# CH573.net
KiCad netlist of a schematic drawn in Altium Designer
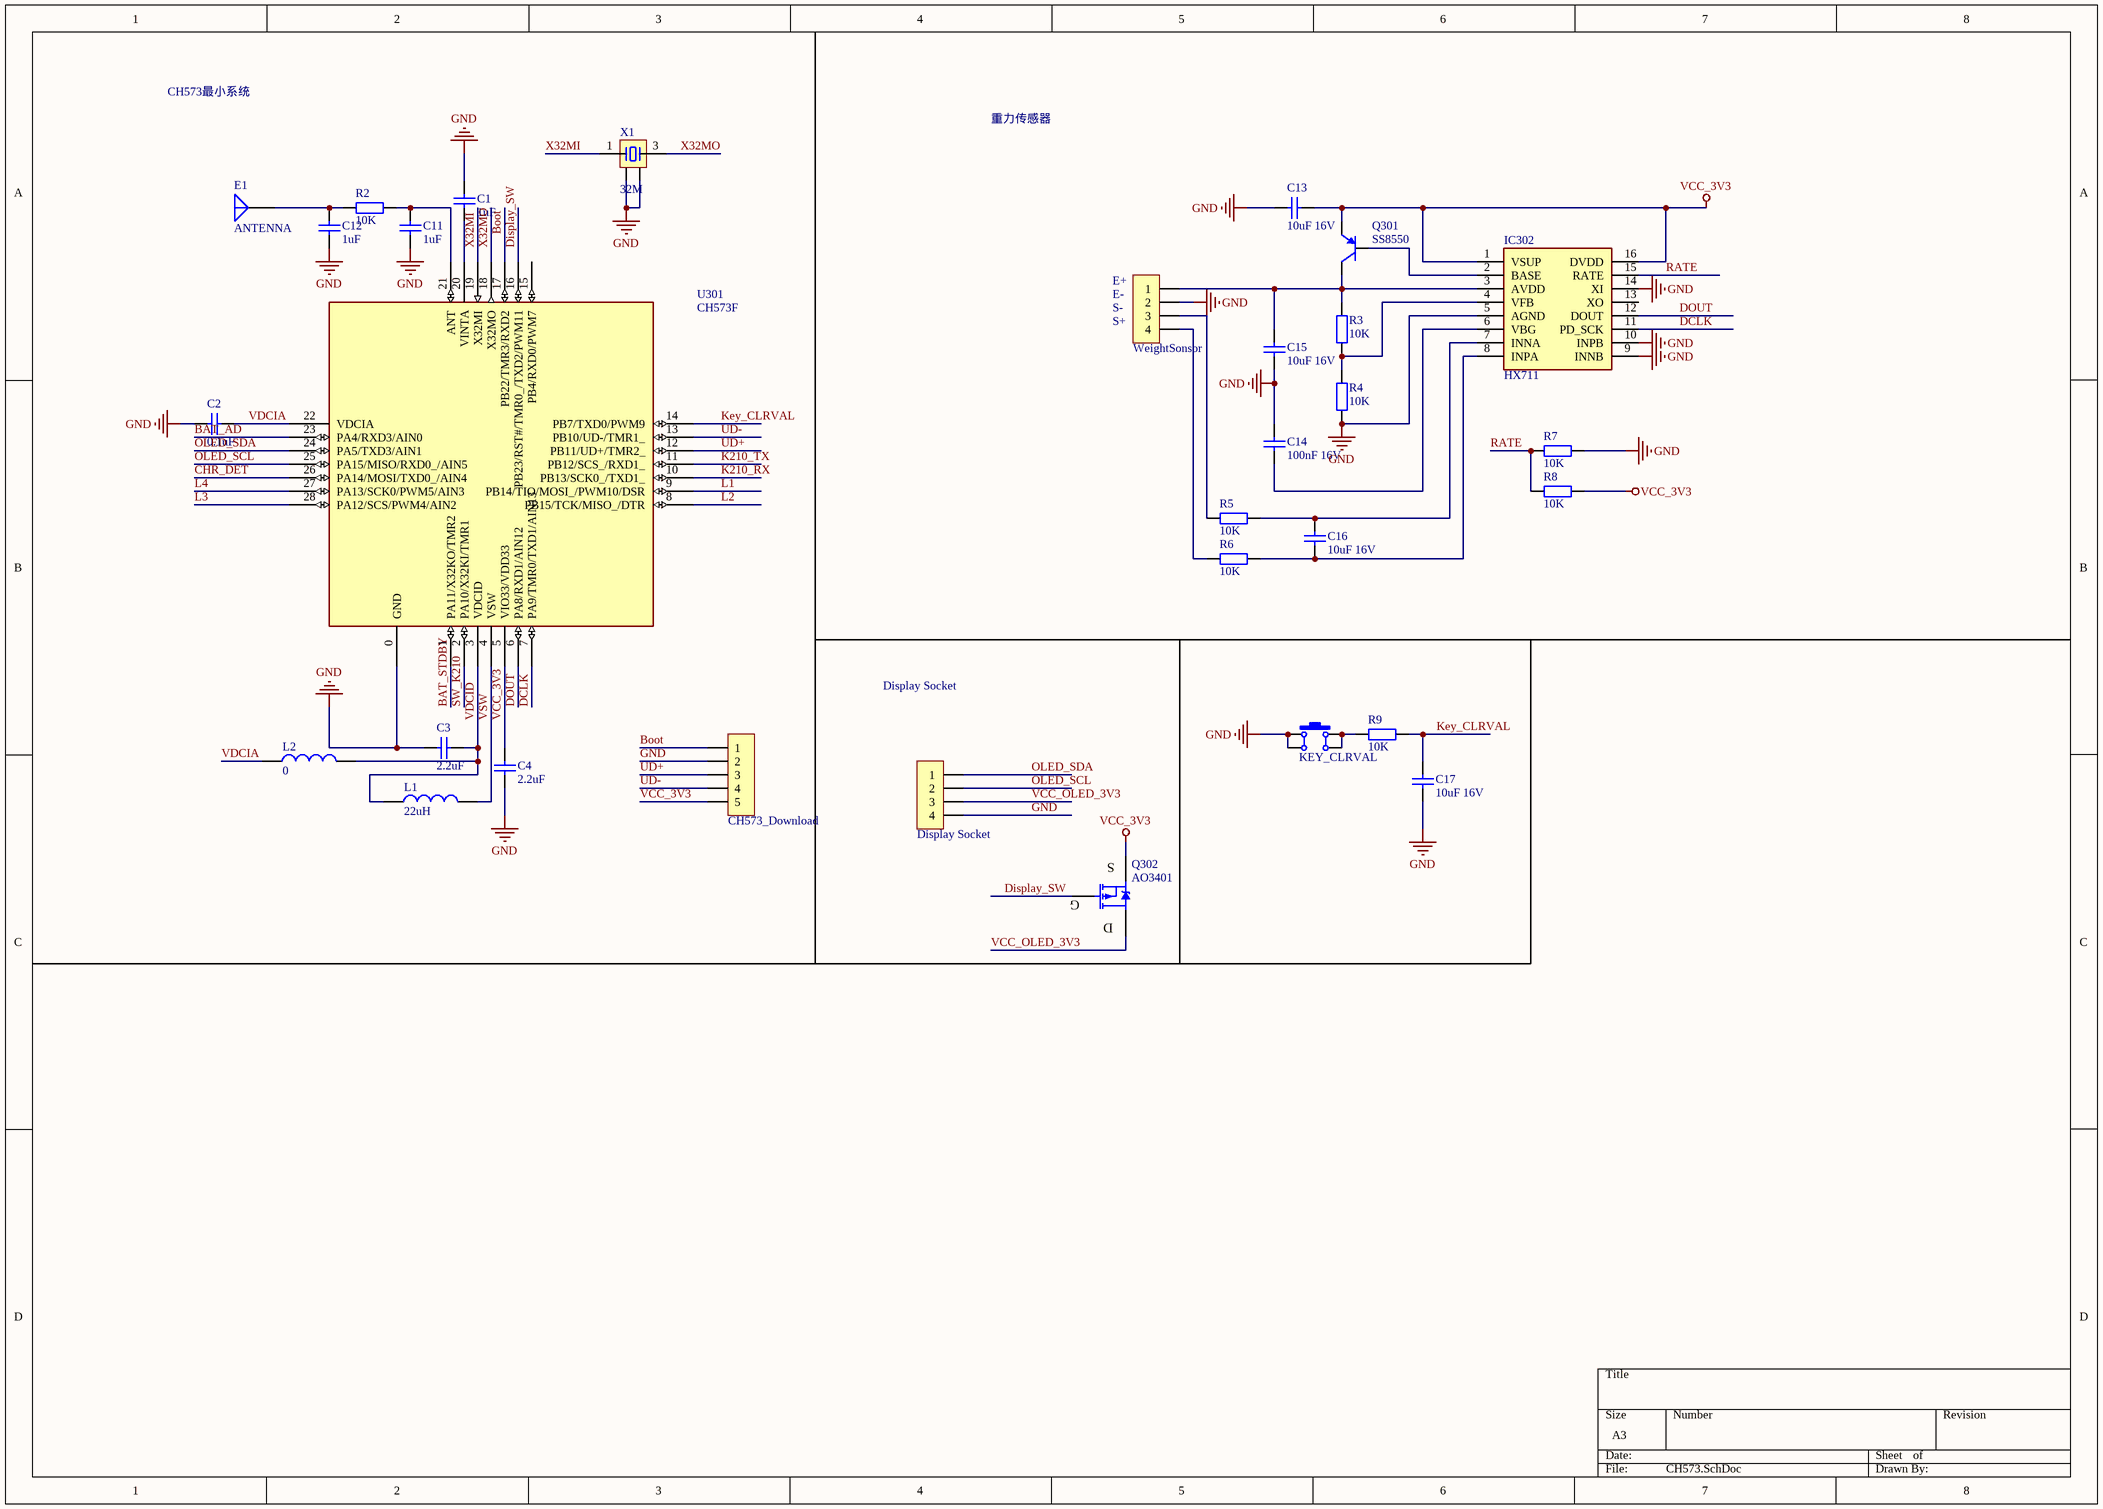
[diagram p0: CH573.SchDoc]

(export (version "E")
  (design (tool "Eeschema 10.0.6"))
  (components
    (comp (ref "C1")
      (value "1uF")
      (footprint "C0603_L")
      (description "贴片电容/MLCC电容")
      (libsource (lib "0.1 - 电阻-电容-电感-晶振-晶体-磁珠-电位器-法拉电容-馈通电容") (part "C"))
    )
    (comp (ref "C2")
      (value "0.1uF")
      (footprint "C0603_L")
      (description "贴片电容/MLCC电容")
      (libsource (lib "0.1 - 电阻-电容-电感-晶振-晶体-磁珠-电位器-法拉电容-馈通电容") (part "C"))
    )
    (comp (ref "C3")
      (value "2.2uF")
      (footprint "C0603_L")
      (description "贴片电容/MLCC电容")
      (libsource (lib "0.1 - 电阻-电容-电感-晶振-晶体-磁珠-电位器-法拉电容-馈通电容") (part "C"))
    )
    (comp (ref "C4")
      (value "2.2uF")
      (footprint "C0603_L")
      (description "贴片电容/MLCC电容")
      (libsource (lib "0.1 - 电阻-电容-电感-晶振-晶体-磁珠-电位器-法拉电容-馈通电容") (part "C"))
    )
    (comp (ref "C11")
      (value "1uF")
      (footprint "C0201_L")
      (description "贴片电容/MLCC电容")
      (libsource (lib "0.1 - 电阻-电容-电感-晶振-晶体-磁珠-电位器-法拉电容-馈通电容") (part "C"))
    )
    (comp (ref "C12")
      (value "1uF")
      (footprint "C0201_L")
      (description "贴片电容/MLCC电容")
      (libsource (lib "0.1 - 电阻-电容-电感-晶振-晶体-磁珠-电位器-法拉电容-馈通电容") (part "C"))
    )
    (comp (ref "C13")
      (value "10uF 16V")
      (footprint "C0805_L")
      (description "贴片电容/MLCC电容")
      (libsource (lib "0.1 - 电阻-电容-电感-晶振-晶体-磁珠-电位器-法拉电容-馈通电容") (part "C"))
    )
    (comp (ref "C14")
      (value "100nF 16V")
      (footprint "C0603_L")
      (description "贴片电容/MLCC电容")
      (libsource (lib "0.1 - 电阻-电容-电感-晶振-晶体-磁珠-电位器-法拉电容-馈通电容") (part "C"))
    )
    (comp (ref "C15")
      (value "10uF 16V")
      (footprint "C0603_L")
      (description "贴片电容/MLCC电容")
      (libsource (lib "0.1 - 电阻-电容-电感-晶振-晶体-磁珠-电位器-法拉电容-馈通电容") (part "C"))
    )
    (comp (ref "C16")
      (value "10uF 16V")
      (footprint "C0603_L")
      (description "贴片电容/MLCC电容")
      (libsource (lib "0.1 - 电阻-电容-电感-晶振-晶体-磁珠-电位器-法拉电容-馈通电容") (part "C"))
    )
    (comp (ref "C17")
      (value "10uF 16V")
      (footprint "C0603_L")
      (description "贴片电容/MLCC电容")
      (libsource (lib "0.1 - 电阻-电容-电感-晶振-晶体-磁珠-电位器-法拉电容-馈通电容") (part "C"))
    )
    (comp (ref "CH573_Download")
      (value "HDR-1X5")
      (footprint "MX1.25-L-5P")
      (description "5P连接器")
      (libsource (lib "5.1 - 1.25mm连接器(FPC1.25_GH1.25_MX1.25)") (part "Header 5"))
    )
    (comp (ref "Display Socket")
      (value "HDR-1X4")
      (footprint "HDR2.54-M-LI-4P")
      (description "4P接插件")
      (libsource (lib "5.5 - 2.54mm连接器(KF2EDGK_XH2.54_2.54排针排母)") (part "Header 4"))
    )
    (comp (ref "E1")
      (value "ANTENNA")
      (footprint "ANT-F-1-2.4G-1.6")
      (description "Generic Antenna")
      (libsource (lib "CH573F-R0") (part "ANTENNA"))
    )
    (comp (ref "IC302")
      (value "HX711")
      (footprint "SamacSys:SOIC127P600X160-16N")
      (description "Integrated Circuit")
      (libsource (lib "SamacSys") (part "HX711"))
    )
    (comp (ref "KEY_CLRVAL")
      (value "4x4x1.5")
      (footprint "SW SMD-4*4*1.5")
      (description "贴片4x4轻触开关")
      (libsource (lib "0.5 - 按键_开关_蜂鸣器_保险丝_电池_测试点_Mark点_铜柱") (part "SW SMD-4x4"))
    )
    (comp (ref "L1")
      (value "22uH")
      (footprint "L0603")
      (description "贴片小功率电感")
      (libsource (lib "0.1 - 电阻-电容-电感-晶振-晶体-磁珠-电位器-法拉电容-馈通电容") (part "L"))
    )
    (comp (ref "L2")
      (value "0")
      (footprint "L0603")
      (description "贴片小功率电感")
      (libsource (lib "0.1 - 电阻-电容-电感-晶振-晶体-磁珠-电位器-法拉电容-馈通电容") (part "L"))
    )
    (comp (ref "Q301")
      (value "SS8550")
      (footprint "SOT23-3N")
      (description "高频放大-PNP型")
      (libsource (lib "0.4 - 三极管-场效应管-可控硅") (part "8550-SMD"))
    )
    (comp (ref "Q302")
      (value "AO3401")
      (footprint "SOT23-3N")
      (description "P沟道 30V/4.2A")
      (libsource (lib "0.4 - 三极管-场效应管-可控硅") (part "AO3401"))
    )
    (comp (ref "R2")
      (value "10K")
      (footprint "R0201_L")
      (description "贴片电阻")
      (libsource (lib "0.1 - 电阻-电容-电感-晶振-晶体-磁珠-电位器-法拉电容-馈通电容") (part "R"))
    )
    (comp (ref "R3")
      (value "10K")
      (footprint "R0603_L")
      (description "贴片电阻")
      (libsource (lib "0.1 - 电阻-电容-电感-晶振-晶体-磁珠-电位器-法拉电容-馈通电容") (part "R"))
    )
    (comp (ref "R4")
      (value "10K")
      (footprint "R0603_L")
      (description "贴片电阻")
      (libsource (lib "0.1 - 电阻-电容-电感-晶振-晶体-磁珠-电位器-法拉电容-馈通电容") (part "R"))
    )
    (comp (ref "R5")
      (value "10K")
      (footprint "R0603_L")
      (description "贴片电阻")
      (libsource (lib "0.1 - 电阻-电容-电感-晶振-晶体-磁珠-电位器-法拉电容-馈通电容") (part "R"))
    )
    (comp (ref "R6")
      (value "10K")
      (footprint "R0603_L")
      (description "贴片电阻")
      (libsource (lib "0.1 - 电阻-电容-电感-晶振-晶体-磁珠-电位器-法拉电容-馈通电容") (part "R"))
    )
    (comp (ref "R7")
      (value "10K")
      (footprint "R0603_L")
      (description "贴片电阻")
      (libsource (lib "0.1 - 电阻-电容-电感-晶振-晶体-磁珠-电位器-法拉电容-馈通电容") (part "R"))
    )
    (comp (ref "R8")
      (value "10K")
      (footprint "R0603_L")
      (description "贴片电阻")
      (libsource (lib "0.1 - 电阻-电容-电感-晶振-晶体-磁珠-电位器-法拉电容-馈通电容") (part "R"))
    )
    (comp (ref "R9")
      (value "10K")
      (footprint "R0603_L")
      (description "贴片电阻")
      (libsource (lib "0.1 - 电阻-电容-电感-晶振-晶体-磁珠-电位器-法拉电容-馈通电容") (part "R"))
    )
    (comp (ref "U301")
      (value "CH573F")
      (footprint "QFN28_4X4")
      (description "RISC-V MCU with BLE/USB/ADC/SPI/4*UART")
      (libsource (lib "CH573F-R0") (part "CH573F"))
    )
    (comp (ref "WeightSonsor")
      (value "HDR-1X4")
      (footprint "XH2.54-LI-4P")
      (description "4P接插件")
      (libsource (lib "5.5 - 2.54mm连接器(KF2EDGK_XH2.54_2.54排针排母)") (part "Header 4"))
    )
    (comp (ref "X1")
      (value "32M")
      (footprint "XTAL-3225-4P")
      (description "4脚无源晶振(谐振器）")
      (libsource (lib "0.1 - 电阻-电容-电感-晶振-晶体-磁珠-电位器-法拉电容-馈通电容") (part "XTAL-4P"))
    )
  )
  (nets
    (net (code "1") (name "/BAT_AD") (class "Default")
      (node (ref "U301") (pin "23") (pinfunction "PA4/RXD3/AIN0_23") (pintype "bidirectional"))
    )
    (net (code "2") (name "/BAT_STDBY") (class "Default")
      (node (ref "U301") (pin "1") (pinfunction "PA11/X32KO/TMR2_1") (pintype "bidirectional"))
    )
    (net (code "3") (name "/Boot") (class "Default")
      (node (ref "CH573_Download") (pin "1") (pinfunction "1_1") (pintype "passive"))
      (node (ref "U301") (pin "17") (pinfunction "PB22/TMR3/RXD2_17") (pintype "bidirectional"))
    )
    (net (code "4") (name "/CHR_DET") (class "Default")
      (node (ref "U301") (pin "26") (pinfunction "PA14/MOSI/TXD0_/AIN4_26") (pintype "bidirectional"))
    )
    (net (code "5") (name "/DCLK") (class "Default")
      (node (ref "IC302") (pin "11") (pinfunction "PD_SCK_11") (pintype "passive"))
      (node (ref "U301") (pin "7") (pinfunction "PA9/TMR0/TXD1/AIN13_7") (pintype "bidirectional"))
    )
    (net (code "6") (name "/DOUT") (class "Default")
      (node (ref "IC302") (pin "12") (pinfunction "DOUT_12") (pintype "passive"))
      (node (ref "U301") (pin "6") (pinfunction "PA8/RXD1/AIN12_6") (pintype "bidirectional"))
    )
    (net (code "7") (name "/Display_SW") (class "Default")
      (node (ref "Q302") (pin "1") (pinfunction "G_1") (pintype "passive"))
      (node (ref "U301") (pin "16") (pinfunction "PB23/RST#/TMR0_/TXD2/PWM11_16") (pintype "bidirectional"))
    )
    (net (code "8") (name "/K210_RX") (class "Default")
      (node (ref "U301") (pin "10") (pinfunction "PB13/SCK0_/TXD1__10") (pintype "bidirectional"))
    )
    (net (code "9") (name "/K210_TX") (class "Default")
      (node (ref "U301") (pin "11") (pinfunction "PB12/SCS_/RXD1__11") (pintype "bidirectional"))
    )
    (net (code "10") (name "/Key_CLRVAL") (class "Default")
      (node (ref "C17") (pin "2") (pinfunction "2_2") (pintype "passive"))
      (node (ref "R9") (pin "1") (pinfunction "1_1") (pintype "passive"))
      (node (ref "U301") (pin "14") (pinfunction "PB7/TXD0/PWM9_14") (pintype "bidirectional"))
    )
    (net (code "11") (name "/L1") (class "Default")
      (node (ref "U301") (pin "9") (pinfunction "PB14/TIO/MOSI_/PWM10/DSR_9") (pintype "bidirectional"))
    )
    (net (code "12") (name "/L2") (class "Default")
      (node (ref "U301") (pin "8") (pinfunction "PB15/TCK/MISO_/DTR_8") (pintype "bidirectional"))
    )
    (net (code "13") (name "/L3") (class "Default")
      (node (ref "U301") (pin "28") (pinfunction "PA12/SCS/PWM4/AIN2_28") (pintype "bidirectional"))
    )
    (net (code "14") (name "/L4") (class "Default")
      (node (ref "U301") (pin "27") (pinfunction "PA13/SCK0/PWM5/AIN3_27") (pintype "bidirectional"))
    )
    (net (code "15") (name "/OLED_SCL") (class "Default")
      (node (ref "Display Socket") (pin "2") (pinfunction "2_2") (pintype "passive"))
      (node (ref "U301") (pin "25") (pinfunction "PA15/MISO/RXD0_/AIN5_25") (pintype "bidirectional"))
    )
    (net (code "16") (name "/OLED_SDA") (class "Default")
      (node (ref "Display Socket") (pin "1") (pinfunction "1_1") (pintype "passive"))
      (node (ref "U301") (pin "24") (pinfunction "PA5/TXD3/AIN1_24") (pintype "bidirectional"))
    )
    (net (code "17") (name "/RATE") (class "Default")
      (node (ref "IC302") (pin "15") (pinfunction "RATE_15") (pintype "passive"))
      (node (ref "R7") (pin "2") (pinfunction "2_2") (pintype "passive"))
      (node (ref "R8") (pin "2") (pinfunction "2_2") (pintype "passive"))
    )
    (net (code "18") (name "/SW_K210") (class "Default")
      (node (ref "U301") (pin "2") (pinfunction "PA10/X32KI/TMR1_2") (pintype "bidirectional"))
    )
    (net (code "19") (name "/UD+") (class "Default")
      (node (ref "CH573_Download") (pin "3") (pinfunction "3_3") (pintype "passive"))
      (node (ref "U301") (pin "12") (pinfunction "PB11/UD+/TMR2__12") (pintype "bidirectional"))
    )
    (net (code "20") (name "/UD-") (class "Default")
      (node (ref "CH573_Download") (pin "4") (pinfunction "4_4") (pintype "passive"))
      (node (ref "U301") (pin "13") (pinfunction "PB10/UD-/TMR1__13") (pintype "bidirectional"))
    )
    (net (code "21") (name "/VCC_OLED_3V3") (class "Default")
      (node (ref "Display Socket") (pin "3") (pinfunction "3_3") (pintype "passive"))
      (node (ref "Q302") (pin "3") (pinfunction "D_3") (pintype "passive"))
    )
    (net (code "22") (name "/VDCIA") (class "Default")
      (node (ref "C2") (pin "1") (pinfunction "1_1") (pintype "passive"))
      (node (ref "L2") (pin "1") (pinfunction "1_1") (pintype "passive"))
      (node (ref "U301") (pin "22") (pinfunction "VDCIA_22") (pintype "power_in"))
    )
    (net (code "23") (name "/VDCID") (class "Default")
      (node (ref "C3") (pin "1") (pinfunction "1_1") (pintype "passive"))
      (node (ref "L1") (pin "1") (pinfunction "1_1") (pintype "passive"))
      (node (ref "L2") (pin "2") (pinfunction "2_2") (pintype "passive"))
      (node (ref "U301") (pin "3") (pinfunction "VDCID_3") (pintype "power_in"))
    )
    (net (code "24") (name "/VSW") (class "Default")
      (node (ref "L1") (pin "2") (pinfunction "2_2") (pintype "passive"))
      (node (ref "U301") (pin "4") (pinfunction "VSW_4") (pintype "power_in"))
    )
    (net (code "25") (name "/X32MI") (class "Default")
      (node (ref "U301") (pin "19") (pinfunction "X32MI_19") (pintype "input"))
      (node (ref "X1") (pin "1") (pinfunction "1_1") (pintype "passive"))
    )
    (net (code "26") (name "/X32MO") (class "Default")
      (node (ref "U301") (pin "18") (pinfunction "X32MO_18") (pintype "output"))
      (node (ref "X1") (pin "3") (pinfunction "3_3") (pintype "passive"))
    )
    (net (code "27") (name "GND") (class "Default")
      (node (ref "C1") (pin "2") (pinfunction "2_2") (pintype "passive"))
      (node (ref "C11") (pin "2") (pinfunction "2_2") (pintype "passive"))
      (node (ref "C12") (pin "2") (pinfunction "2_2") (pintype "passive"))
      (node (ref "C13") (pin "1") (pinfunction "1_1") (pintype "passive"))
      (node (ref "C14") (pin "2") (pinfunction "2_2") (pintype "passive"))
      (node (ref "C15") (pin "1") (pinfunction "1_1") (pintype "passive"))
      (node (ref "C17") (pin "1") (pinfunction "1_1") (pintype "passive"))
      (node (ref "C2") (pin "2") (pinfunction "2_2") (pintype "passive"))
      (node (ref "C3") (pin "2") (pinfunction "2_2") (pintype "passive"))
      (node (ref "C4") (pin "2") (pinfunction "2_2") (pintype "passive"))
      (node (ref "CH573_Download") (pin "2") (pinfunction "2_2") (pintype "passive"))
      (node (ref "Display Socket") (pin "4") (pinfunction "4_4") (pintype "passive"))
      (node (ref "IC302") (pin "10") (pinfunction "INPB_10") (pintype "passive"))
      (node (ref "IC302") (pin "14") (pinfunction "XI_14") (pintype "passive"))
      (node (ref "IC302") (pin "5") (pinfunction "AGND_5") (pintype "passive"))
      (node (ref "IC302") (pin "9") (pinfunction "INNB_9") (pintype "passive"))
      (node (ref "KEY_CLRVAL") (pin "1") (pinfunction "1_1") (pintype "passive"))
      (node (ref "KEY_CLRVAL") (pin "4") (pinfunction "4_4") (pintype "passive"))
      (node (ref "R4") (pin "1") (pinfunction "1_1") (pintype "passive"))
      (node (ref "R7") (pin "1") (pinfunction "1_1") (pintype "passive"))
      (node (ref "U301") (pin "0") (pinfunction "GND_0") (pintype "power_in"))
      (node (ref "WeightSonsor") (pin "2") (pinfunction "2_2") (pintype "passive"))
      (node (ref "X1") (pin "2") (pinfunction "2_2") (pintype "passive"))
      (node (ref "X1") (pin "4") (pinfunction "4_4") (pintype "passive"))
    )
    (net (code "28") (name "Net-(E1-A)") (class "Default")
      (node (ref "C12") (pin "1") (pinfunction "1_1") (pintype "passive"))
      (node (ref "E1") (pin "1") (pinfunction "A_1") (pintype "passive"))
      (node (ref "R2") (pin "1") (pinfunction "1_1") (pintype "passive"))
    )
    (net (code "29") (name "Net-(IC302-AVDD)") (class "Default")
      (node (ref "C15") (pin "2") (pinfunction "2_2") (pintype "passive"))
      (node (ref "IC302") (pin "3") (pinfunction "AVDD_3") (pintype "passive"))
      (node (ref "Q301") (pin "3") (pinfunction "C_3") (pintype "passive"))
      (node (ref "R3") (pin "2") (pinfunction "2_2") (pintype "passive"))
      (node (ref "WeightSonsor") (pin "1") (pinfunction "1_1") (pintype "passive"))
    )
    (net (code "30") (name "Net-(IC302-BASE)") (class "Default")
      (node (ref "IC302") (pin "2") (pinfunction "BASE_2") (pintype "passive"))
      (node (ref "Q301") (pin "1") (pinfunction "B_1") (pintype "passive"))
    )
    (net (code "31") (name "Net-(IC302-INNA)") (class "Default")
      (node (ref "C16") (pin "2") (pinfunction "2_2") (pintype "passive"))
      (node (ref "IC302") (pin "7") (pinfunction "INNA_7") (pintype "passive"))
      (node (ref "R5") (pin "1") (pinfunction "1_1") (pintype "passive"))
    )
    (net (code "32") (name "Net-(IC302-INPA)") (class "Default")
      (node (ref "C16") (pin "1") (pinfunction "1_1") (pintype "passive"))
      (node (ref "IC302") (pin "8") (pinfunction "INPA_8") (pintype "passive"))
      (node (ref "R6") (pin "1") (pinfunction "1_1") (pintype "passive"))
    )
    (net (code "33") (name "Net-(IC302-VBG)") (class "Default")
      (node (ref "C14") (pin "1") (pinfunction "1_1") (pintype "passive"))
      (node (ref "IC302") (pin "6") (pinfunction "VBG_6") (pintype "passive"))
    )
    (net (code "34") (name "Net-(IC302-VFB)") (class "Default")
      (node (ref "IC302") (pin "4") (pinfunction "VFB_4") (pintype "passive"))
      (node (ref "R3") (pin "1") (pinfunction "1_1") (pintype "passive"))
      (node (ref "R4") (pin "2") (pinfunction "2_2") (pintype "passive"))
    )
    (net (code "35") (name "Net-(KEY_CLRVAL-Pad2)") (class "Default")
      (node (ref "KEY_CLRVAL") (pin "2") (pinfunction "2_2") (pintype "passive"))
      (node (ref "KEY_CLRVAL") (pin "3") (pinfunction "3_3") (pintype "passive"))
      (node (ref "R9") (pin "2") (pinfunction "2_2") (pintype "passive"))
    )
    (net (code "36") (name "Net-(R5-Pad2)") (class "Default")
      (node (ref "R5") (pin "2") (pinfunction "2_2") (pintype "passive"))
      (node (ref "WeightSonsor") (pin "3") (pinfunction "3_3") (pintype "passive"))
    )
    (net (code "37") (name "Net-(R6-Pad2)") (class "Default")
      (node (ref "R6") (pin "2") (pinfunction "2_2") (pintype "passive"))
      (node (ref "WeightSonsor") (pin "4") (pinfunction "4_4") (pintype "passive"))
    )
    (net (code "38") (name "Net-(U301-ANT)") (class "Default")
      (node (ref "C11") (pin "1") (pinfunction "1_1") (pintype "passive"))
      (node (ref "R2") (pin "2") (pinfunction "2_2") (pintype "passive"))
      (node (ref "U301") (pin "21") (pinfunction "ANT_21") (pintype "bidirectional"))
    )
    (net (code "39") (name "Net-(U301-VINTA)") (class "Default")
      (node (ref "C1") (pin "1") (pinfunction "1_1") (pintype "passive"))
      (node (ref "U301") (pin "20") (pinfunction "VINTA_20") (pintype "power_in"))
    )
    (net (code "40") (name "VCC_3V3") (class "Default")
      (node (ref "C13") (pin "2") (pinfunction "2_2") (pintype "passive"))
      (node (ref "C4") (pin "1") (pinfunction "1_1") (pintype "passive"))
      (node (ref "CH573_Download") (pin "5") (pinfunction "5_5") (pintype "passive"))
      (node (ref "IC302") (pin "1") (pinfunction "VSUP_1") (pintype "passive"))
      (node (ref "IC302") (pin "16") (pinfunction "DVDD_16") (pintype "passive"))
      (node (ref "Q301") (pin "2") (pinfunction "E_2") (pintype "passive"))
      (node (ref "Q302") (pin "2") (pinfunction "S_2") (pintype "passive"))
      (node (ref "R8") (pin "1") (pinfunction "1_1") (pintype "passive"))
      (node (ref "U301") (pin "5") (pinfunction "VIO33/VDD33_5") (pintype "power_in"))
    )
    (net (code "41") (name "unconnected-(IC302-XO-Pad13)") (class "Default")
      (node (ref "IC302") (pin "13") (pinfunction "XO_13") (pintype "passive"))
    )
    (net (code "42") (name "unconnected-(U301-PB4{slash}RXD0{slash}PWM7-Pad15)") (class "Default")
      (node (ref "U301") (pin "15") (pinfunction "PB4/RXD0/PWM7_15") (pintype "bidirectional"))
    )
  )
)
